# Connectors.net
KiCad netlist of a schematic drawn in Altium Designer
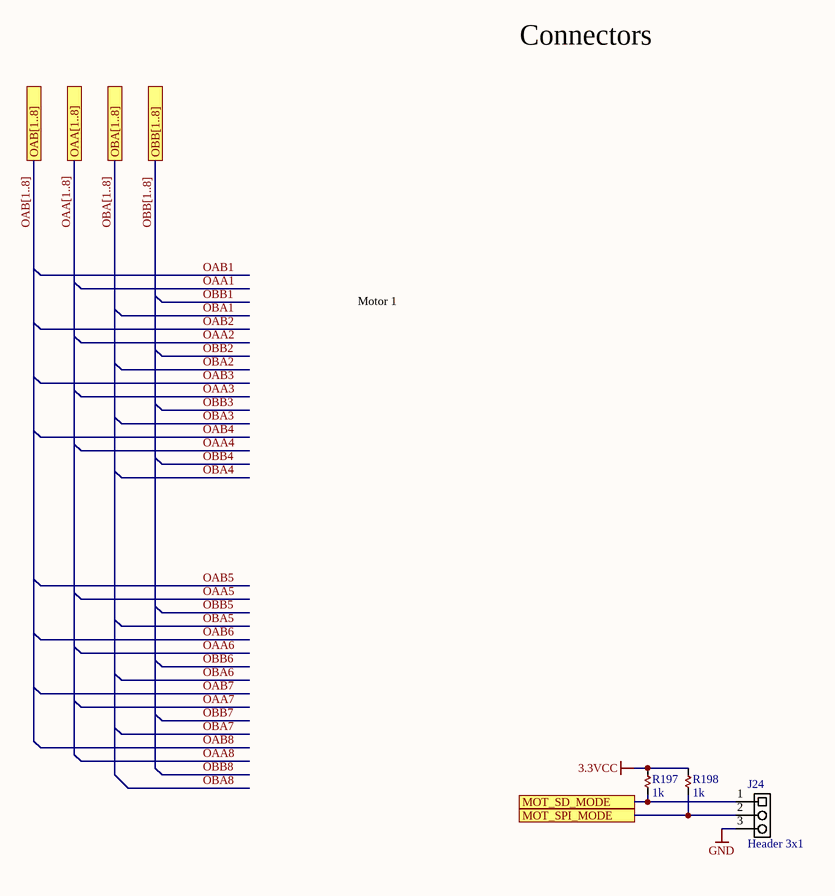
[diagram p0: Connectors.SchDoc]

(export (version "E")
  (design (tool "Eeschema 10.0.6"))
  (components
    (comp (ref "J24")
      (value "Header 3x1")
      (footprint "HDR3X1")
      (description "Header 3Pin 1Row T-Hole")
      (fields (field (name "MANUFACTURER") "Multicomp") (field (name "PART") "2211S-03G"))
      (libsource (lib "Connectors") (part "Header 3x1 Male Pin"))
    )
    (comp (ref "R197")
      (value "1k")
      (footprint "R0402")
      (description "RES 0402 1k 63mW 1%")
      (fields (field (name "MANUFACTURER") "Yageo") (field (name "PART") "RC0402FR-071KL"))
      (libsource (lib "Resistors") (part "1k 1% 0402"))
    )
    (comp (ref "R198")
      (value "1k")
      (footprint "R0402")
      (description "RES 0402 1k 63mW 1%")
      (fields (field (name "MANUFACTURER") "Yageo") (field (name "PART") "RC0402FR-071KL"))
      (libsource (lib "Resistors") (part "1k 1% 0402"))
    )
  )
  (nets
    (net (code "1") (name "/MOT_SD_MODE") (class "Default")
      (node (ref "J24") (pin "1") (pinfunction "1_1") (pintype "passive"))
      (node (ref "R197") (pin "1") (pinfunction "1_1") (pintype "passive"))
    )
    (net (code "2") (name "/MOT_SPI_MODE") (class "Default")
      (node (ref "J24") (pin "2") (pinfunction "2_2") (pintype "passive"))
      (node (ref "R198") (pin "1") (pinfunction "1_1") (pintype "passive"))
    )
    (net (code "39") (name "3.3VCC") (class "Default")
      (node (ref "R197") (pin "2") (pinfunction "2_2") (pintype "passive"))
      (node (ref "R198") (pin "2") (pinfunction "2_2") (pintype "passive"))
    )
    (net (code "40") (name "GND") (class "Default")
      (node (ref "J24") (pin "3") (pinfunction "3_3") (pintype "passive"))
    )
  )
)
